# modular_expansion_system_esp32.net
KiCad netlist of a schematic drawn in EAGLE
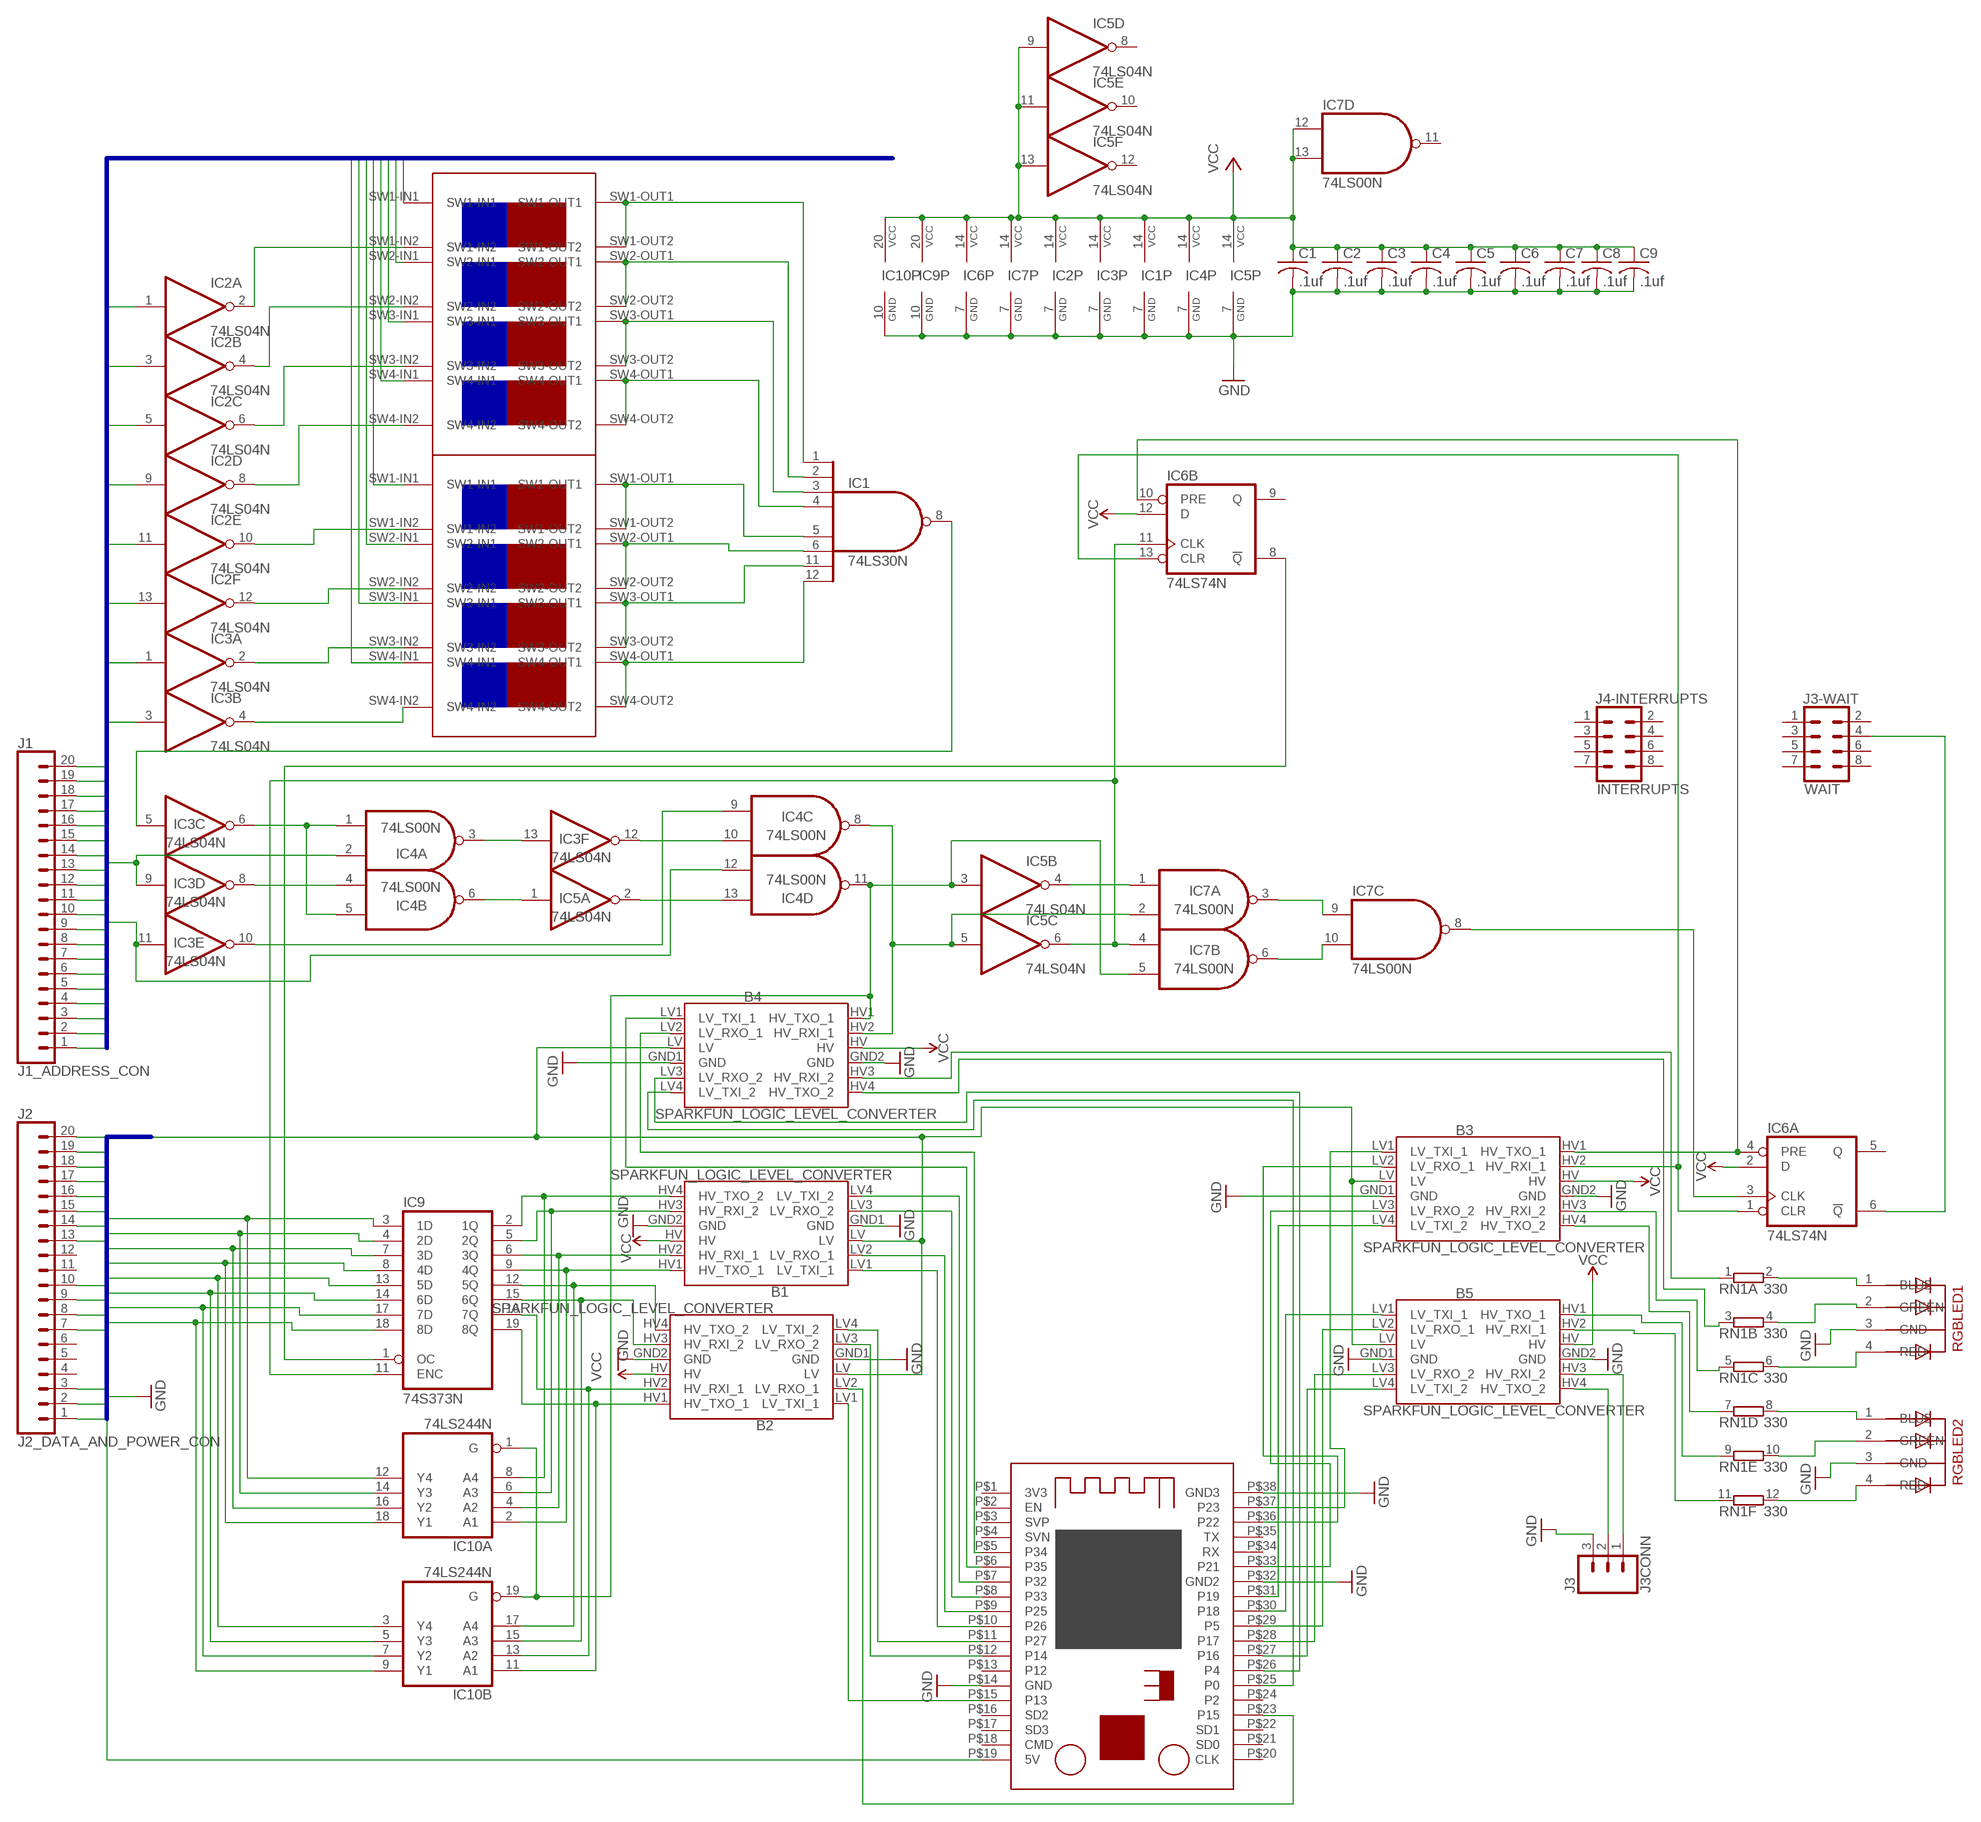
[diagram p0: schematic, sheet 1]

(export (version "E")
  (design (tool "Eeschema 10.0.6"))
  (components
    (comp (ref "B1")
      (value "SPARKFUN_LOGIC_LEVEL_CONVERTER")
      (footprint "eagle-import:SPARKFUN_LOGIC_LEVEL_CONVERTER")
      (libsource (lib "eagle-import") (part "SPARKFUN_LOGIC_LEVEL_CONVERTER"))
    )
    (comp (ref "B2")
      (value "SPARKFUN_LOGIC_LEVEL_CONVERTER")
      (footprint "eagle-import:SPARKFUN_LOGIC_LEVEL_CONVERTER")
      (libsource (lib "eagle-import") (part "SPARKFUN_LOGIC_LEVEL_CONVERTER"))
    )
    (comp (ref "B3")
      (value "SPARKFUN_LOGIC_LEVEL_CONVERTER")
      (footprint "eagle-import:SPARKFUN_LOGIC_LEVEL_CONVERTER")
      (libsource (lib "eagle-import") (part "SPARKFUN_LOGIC_LEVEL_CONVERTER"))
    )
    (comp (ref "B4")
      (value "SPARKFUN_LOGIC_LEVEL_CONVERTER")
      (footprint "eagle-import:SPARKFUN_LOGIC_LEVEL_CONVERTER")
      (libsource (lib "eagle-import") (part "SPARKFUN_LOGIC_LEVEL_CONVERTER"))
    )
    (comp (ref "B5")
      (value "SPARKFUN_LOGIC_LEVEL_CONVERTER")
      (footprint "eagle-import:SPARKFUN_LOGIC_LEVEL_CONVERTER")
      (libsource (lib "eagle-import") (part "SPARKFUN_LOGIC_LEVEL_CONVERTER"))
    )
    (comp (ref "C1")
      (value ".1uf")
      (footprint "eagle-import:C025-025X050")
      (libsource (lib "eagle-import") (part "C-US025-025X050"))
    )
    (comp (ref "C2")
      (value ".1uf")
      (footprint "eagle-import:C025-025X050")
      (libsource (lib "eagle-import") (part "C-US025-025X050"))
    )
    (comp (ref "C3")
      (value ".1uf")
      (footprint "eagle-import:C025-025X050")
      (libsource (lib "eagle-import") (part "C-US025-025X050"))
    )
    (comp (ref "C4")
      (value ".1uf")
      (footprint "eagle-import:C025-025X050")
      (libsource (lib "eagle-import") (part "C-US025-025X050"))
    )
    (comp (ref "C5")
      (value ".1uf")
      (footprint "eagle-import:C025-025X050")
      (libsource (lib "eagle-import") (part "C-US025-025X050"))
    )
    (comp (ref "C6")
      (value ".1uf")
      (footprint "eagle-import:C025-025X050")
      (libsource (lib "eagle-import") (part "C-US025-025X050"))
    )
    (comp (ref "C7")
      (value ".1uf")
      (footprint "eagle-import:C025-025X050")
      (libsource (lib "eagle-import") (part "C-US025-025X050"))
    )
    (comp (ref "C8")
      (value ".1uf")
      (footprint "eagle-import:C025-025X050")
      (libsource (lib "eagle-import") (part "C-US025-025X050"))
    )
    (comp (ref "C9")
      (value ".1uf")
      (footprint "eagle-import:C025-025X050")
      (libsource (lib "eagle-import") (part "C-US025-025X050"))
    )
    (comp (ref "IC1")
      (value "74LS30N")
      (footprint "eagle-import:DIL14")
      (libsource (lib "eagle-import") (part "7430NLS"))
    )
    (comp (ref "IC2")
      (value "74LS04N")
      (footprint "eagle-import:DIL14")
      (libsource (lib "eagle-import") (part "7404NLS"))
    )
    (comp (ref "IC3")
      (value "74LS04N")
      (footprint "eagle-import:DIL14")
      (libsource (lib "eagle-import") (part "7404NLS"))
    )
    (comp (ref "IC4")
      (value "74LS00N")
      (footprint "eagle-import:DIL14")
      (libsource (lib "eagle-import") (part "7400NLS"))
    )
    (comp (ref "IC5")
      (value "74LS04N")
      (footprint "eagle-import:DIL14")
      (libsource (lib "eagle-import") (part "7404NLS"))
    )
    (comp (ref "IC6")
      (value "74LS74N")
      (footprint "eagle-import:DIL14")
      (libsource (lib "eagle-import") (part "7474NLS"))
    )
    (comp (ref "IC7")
      (value "74LS00N")
      (footprint "eagle-import:DIL14")
      (libsource (lib "eagle-import") (part "7400NLS"))
    )
    (comp (ref "IC9")
      (value "74S373N")
      (footprint "eagle-import:DIL20")
      (libsource (lib "eagle-import") (part "74373NS"))
    )
    (comp (ref "IC10")
      (value "74LS244N")
      (footprint "eagle-import:DIL20")
      (libsource (lib "eagle-import") (part "74244NLS"))
    )
    (comp (ref "J1")
      (value "J1_ADDRESS_CON")
      (footprint "eagle-import:1X20")
      (libsource (lib "eagle-import") (part "CONN_20"))
    )
    (comp (ref "J2")
      (value "J2_DATA_AND_POWER_CON")
      (footprint "eagle-import:1X20")
      (libsource (lib "eagle-import") (part "CONN_20"))
    )
    (comp (ref "J3")
      (value "J3CONN")
      (footprint "eagle-import:1X03")
      (libsource (lib "eagle-import") (part "CONN_03"))
    )
    (comp (ref "J3-WAIT")
      (value "WAIT")
      (footprint "eagle-import:2X4")
      (libsource (lib "eagle-import") (part "CONN_04X2"))
    )
    (comp (ref "J4-INTERRUPTS")
      (value "INTERRUPTS")
      (footprint "eagle-import:2X4")
      (libsource (lib "eagle-import") (part "CONN_04X2"))
    )
    (comp (ref "RGBLED1")
      (value "5MMRGBLED")
      (footprint "eagle-import:LED5MMRGB")
      (libsource (lib "eagle-import") (part "5MMRGBLED"))
    )
    (comp (ref "RGBLED2")
      (value "5MMRGBLED")
      (footprint "eagle-import:LED5MMRGB")
      (libsource (lib "eagle-import") (part "5MMRGBLED"))
    )
    (comp (ref "RN1")
      (value "330")
      (footprint "eagle-import:SIL12")
      (libsource (lib "eagle-import") (part "E6R"))
    )
    (comp (ref "SW1")
      (value "CTS206-124")
      (footprint "eagle-import:CTS206-124")
      (libsource (lib "eagle-import") (part "CTS206-124"))
    )
    (comp (ref "SW2")
      (value "CTS206-124")
      (footprint "eagle-import:CTS206-124")
      (libsource (lib "eagle-import") (part "CTS206-124"))
    )
    (comp (ref "U$1")
      (value "ESP32S")
      (footprint "eagle-import:ESP32S")
      (libsource (lib "eagle-import") (part "ESP32S"))
    )
  )
  (nets
    (net (code "1") (name "/A0") (class "Default")
      (node (ref "IC3") (pin "3") (pinfunction "I_3") (pintype "input"))
      (node (ref "J1") (pin "1") (pinfunction "1_1") (pintype "passive"))
      (node (ref "SW1") (pin "SW4-IN1") (pinfunction "SW4-IN1_SW4-IN1") (pintype "bidirectional"))
    )
    (net (code "2") (name "/A1") (class "Default")
      (node (ref "IC3") (pin "1") (pinfunction "I_1") (pintype "input"))
      (node (ref "J1") (pin "2") (pinfunction "2_2") (pintype "passive"))
      (node (ref "SW1") (pin "SW3-IN1") (pinfunction "SW3-IN1_SW3-IN1") (pintype "bidirectional"))
    )
    (net (code "3") (name "/A2") (class "Default")
      (node (ref "IC2") (pin "13") (pinfunction "I_13") (pintype "input"))
      (node (ref "J1") (pin "3") (pinfunction "3_3") (pintype "passive"))
      (node (ref "SW1") (pin "SW2-IN1") (pinfunction "SW2-IN1_SW2-IN1") (pintype "bidirectional"))
    )
    (net (code "4") (name "/A3") (class "Default")
      (node (ref "IC2") (pin "11") (pinfunction "I_11") (pintype "input"))
      (node (ref "J1") (pin "4") (pinfunction "4_4") (pintype "passive"))
      (node (ref "SW1") (pin "SW1-IN1") (pinfunction "SW1-IN1_SW1-IN1") (pintype "bidirectional"))
    )
    (net (code "5") (name "/A4") (class "Default")
      (node (ref "IC2") (pin "9") (pinfunction "I_9") (pintype "input"))
      (node (ref "J1") (pin "5") (pinfunction "5_5") (pintype "passive"))
      (node (ref "SW2") (pin "SW4-IN1") (pinfunction "SW4-IN1_SW4-IN1") (pintype "bidirectional"))
    )
    (net (code "6") (name "/A5") (class "Default")
      (node (ref "IC2") (pin "5") (pinfunction "I_5") (pintype "input"))
      (node (ref "J1") (pin "6") (pinfunction "6_6") (pintype "passive"))
      (node (ref "SW2") (pin "SW3-IN1") (pinfunction "SW3-IN1_SW3-IN1") (pintype "bidirectional"))
    )
    (net (code "7") (name "/A6") (class "Default")
      (node (ref "IC2") (pin "3") (pinfunction "I_3") (pintype "input"))
      (node (ref "J1") (pin "7") (pinfunction "7_7") (pintype "passive"))
      (node (ref "SW2") (pin "SW2-IN1") (pinfunction "SW2-IN1_SW2-IN1") (pintype "bidirectional"))
    )
    (net (code "8") (name "/A7") (class "Default")
      (node (ref "IC2") (pin "1") (pinfunction "I_1") (pintype "input"))
      (node (ref "J1") (pin "8") (pinfunction "8_8") (pintype "passive"))
      (node (ref "SW2") (pin "SW1-IN1") (pinfunction "SW1-IN1_SW1-IN1") (pintype "bidirectional"))
    )
    (net (code "9") (name "/D0") (class "Default")
      (node (ref "IC10") (pin "9") (pinfunction "Y1_9") (pintype "tri_state"))
      (node (ref "IC9") (pin "18") (pinfunction "8D_18") (pintype "input"))
      (node (ref "J2") (pin "20") (pinfunction "20_20") (pintype "passive"))
    )
    (net (code "10") (name "/D1") (class "Default")
      (node (ref "IC10") (pin "7") (pinfunction "Y2_7") (pintype "tri_state"))
      (node (ref "IC9") (pin "17") (pinfunction "7D_17") (pintype "input"))
      (node (ref "J2") (pin "19") (pinfunction "19_19") (pintype "passive"))
    )
    (net (code "11") (name "/D2") (class "Default")
      (node (ref "IC10") (pin "5") (pinfunction "Y3_5") (pintype "tri_state"))
      (node (ref "IC9") (pin "14") (pinfunction "6D_14") (pintype "input"))
      (node (ref "J2") (pin "18") (pinfunction "18_18") (pintype "passive"))
    )
    (net (code "12") (name "/D3") (class "Default")
      (node (ref "IC10") (pin "3") (pinfunction "Y4_3") (pintype "tri_state"))
      (node (ref "IC9") (pin "13") (pinfunction "5D_13") (pintype "input"))
      (node (ref "J2") (pin "17") (pinfunction "17_17") (pintype "passive"))
    )
    (net (code "13") (name "/D4") (class "Default")
      (node (ref "IC10") (pin "18") (pinfunction "Y1_18") (pintype "tri_state"))
      (node (ref "IC9") (pin "8") (pinfunction "4D_8") (pintype "input"))
      (node (ref "J2") (pin "16") (pinfunction "16_16") (pintype "passive"))
    )
    (net (code "14") (name "/D5") (class "Default")
      (node (ref "IC10") (pin "16") (pinfunction "Y2_16") (pintype "tri_state"))
      (node (ref "IC9") (pin "7") (pinfunction "3D_7") (pintype "input"))
      (node (ref "J2") (pin "15") (pinfunction "15_15") (pintype "passive"))
    )
    (net (code "15") (name "/D6") (class "Default")
      (node (ref "IC10") (pin "14") (pinfunction "Y3_14") (pintype "tri_state"))
      (node (ref "IC9") (pin "4") (pinfunction "2D_4") (pintype "input"))
      (node (ref "J2") (pin "14") (pinfunction "14_14") (pintype "passive"))
    )
    (net (code "16") (name "/D7") (class "Default")
      (node (ref "IC10") (pin "12") (pinfunction "Y4_12") (pintype "tri_state"))
      (node (ref "IC9") (pin "3") (pinfunction "1D_3") (pintype "input"))
      (node (ref "J2") (pin "13") (pinfunction "13_13") (pintype "passive"))
    )
    (net (code "17") (name "/IN_") (class "Default")
      (node (ref "IC3") (pin "9") (pinfunction "I_9") (pintype "input"))
      (node (ref "IC4") (pin "2") (pinfunction "I1_2") (pintype "input"))
      (node (ref "J1") (pin "17") (pinfunction "17_17") (pintype "passive"))
    )
    (net (code "18") (name "/OUT_") (class "Default")
      (node (ref "IC3") (pin "11") (pinfunction "I_11") (pintype "input"))
      (node (ref "IC4") (pin "12") (pinfunction "I0_12") (pintype "input"))
      (node (ref "J1") (pin "18") (pinfunction "18_18") (pintype "passive"))
    )
    (net (code "19") (name "/VCC{slash}2") (class "Default")
      (node (ref "B1") (pin "LV") (pinfunction "LV_LV") (pintype "power_in"))
      (node (ref "B2") (pin "LV") (pinfunction "LV_LV") (pintype "power_in"))
      (node (ref "B3") (pin "LV") (pinfunction "LV_LV") (pintype "power_in"))
      (node (ref "B4") (pin "LV") (pinfunction "LV_LV") (pintype "power_in"))
      (node (ref "B5") (pin "LV") (pinfunction "LV_LV") (pintype "power_in"))
      (node (ref "J2") (pin "3") (pinfunction "3_3") (pintype "passive"))
    )
    (net (code "20") (name "GND") (class "Default")
      (node (ref "B1") (pin "GND1") (pinfunction "GND_GND1") (pintype "power_in"))
      (node (ref "B1") (pin "GND2") (pinfunction "GND_GND2") (pintype "power_in"))
      (node (ref "B2") (pin "GND1") (pinfunction "GND_GND1") (pintype "power_in"))
      (node (ref "B2") (pin "GND2") (pinfunction "GND_GND2") (pintype "power_in"))
      (node (ref "B3") (pin "GND1") (pinfunction "GND_GND1") (pintype "power_in"))
      (node (ref "B3") (pin "GND2") (pinfunction "GND_GND2") (pintype "power_in"))
      (node (ref "B4") (pin "GND1") (pinfunction "GND_GND1") (pintype "power_in"))
      (node (ref "B4") (pin "GND2") (pinfunction "GND_GND2") (pintype "power_in"))
      (node (ref "B5") (pin "GND1") (pinfunction "GND_GND1") (pintype "power_in"))
      (node (ref "B5") (pin "GND2") (pinfunction "GND_GND2") (pintype "power_in"))
      (node (ref "C1") (pin "2") (pinfunction "2_2") (pintype "passive"))
      (node (ref "C2") (pin "2") (pinfunction "2_2") (pintype "passive"))
      (node (ref "C3") (pin "2") (pinfunction "2_2") (pintype "passive"))
      (node (ref "C4") (pin "2") (pinfunction "2_2") (pintype "passive"))
      (node (ref "C5") (pin "2") (pinfunction "2_2") (pintype "passive"))
      (node (ref "C6") (pin "2") (pinfunction "2_2") (pintype "passive"))
      (node (ref "C7") (pin "2") (pinfunction "2_2") (pintype "passive"))
      (node (ref "C8") (pin "2") (pinfunction "2_2") (pintype "passive"))
      (node (ref "C9") (pin "2") (pinfunction "2_2") (pintype "passive"))
      (node (ref "IC1") (pin "7") (pinfunction "GND_7") (pintype "power_in"))
      (node (ref "IC10") (pin "10") (pinfunction "GND_10") (pintype "power_in"))
      (node (ref "IC2") (pin "7") (pinfunction "GND_7") (pintype "power_in"))
      (node (ref "IC3") (pin "7") (pinfunction "GND_7") (pintype "power_in"))
      (node (ref "IC4") (pin "7") (pinfunction "GND_7") (pintype "power_in"))
      (node (ref "IC5") (pin "7") (pinfunction "GND_7") (pintype "power_in"))
      (node (ref "IC6") (pin "7") (pinfunction "GND_7") (pintype "power_in"))
      (node (ref "IC7") (pin "7") (pinfunction "GND_7") (pintype "power_in"))
      (node (ref "IC9") (pin "10") (pinfunction "GND_10") (pintype "power_in"))
      (node (ref "J2") (pin "2") (pinfunction "2_2") (pintype "passive"))
      (node (ref "J3") (pin "3") (pinfunction "3_3") (pintype "passive"))
      (node (ref "RGBLED1") (pin "3") (pinfunction "GND_3") (pintype "bidirectional"))
      (node (ref "RGBLED2") (pin "3") (pinfunction "GND_3") (pintype "bidirectional"))
      (node (ref "U$1") (pin "P$14") (pinfunction "GND_P$14") (pintype "bidirectional"))
      (node (ref "U$1") (pin "P$32") (pinfunction "GND2_P$32") (pintype "bidirectional"))
      (node (ref "U$1") (pin "P$38") (pinfunction "GND3_P$38") (pintype "bidirectional"))
    )
    (net (code "21") (name "Net-(B1-HV_RXI_1)") (class "Default")
      (node (ref "B1") (pin "HV2") (pinfunction "HV_RXI_1_HV2") (pintype "bidirectional"))
      (node (ref "IC10") (pin "4") (pinfunction "A2_4") (pintype "input"))
      (node (ref "IC9") (pin "6") (pinfunction "3Q_6") (pintype "tri_state"))
    )
    (net (code "22") (name "Net-(B1-HV_RXI_2)") (class "Default")
      (node (ref "B1") (pin "HV3") (pinfunction "HV_RXI_2_HV3") (pintype "bidirectional"))
      (node (ref "IC10") (pin "6") (pinfunction "A3_6") (pintype "input"))
      (node (ref "IC9") (pin "5") (pinfunction "2Q_5") (pintype "tri_state"))
    )
    (net (code "23") (name "Net-(B1-HV_TXO_1)") (class "Default")
      (node (ref "B1") (pin "HV1") (pinfunction "HV_TXO_1_HV1") (pintype "bidirectional"))
      (node (ref "IC10") (pin "2") (pinfunction "A1_2") (pintype "input"))
      (node (ref "IC9") (pin "9") (pinfunction "4Q_9") (pintype "tri_state"))
    )
    (net (code "24") (name "Net-(B1-HV_TXO_2)") (class "Default")
      (node (ref "B1") (pin "HV4") (pinfunction "HV_TXO_2_HV4") (pintype "bidirectional"))
      (node (ref "IC10") (pin "8") (pinfunction "A4_8") (pintype "input"))
      (node (ref "IC9") (pin "2") (pinfunction "1Q_2") (pintype "tri_state"))
    )
    (net (code "25") (name "Net-(B1-LV_RXO_1)") (class "Default")
      (node (ref "B1") (pin "LV2") (pinfunction "LV_RXO_1_LV2") (pintype "bidirectional"))
      (node (ref "U$1") (pin "P$9") (pinfunction "P25_P$9") (pintype "bidirectional"))
    )
    (net (code "26") (name "Net-(B1-LV_RXO_2)") (class "Default")
      (node (ref "B1") (pin "LV3") (pinfunction "LV_RXO_2_LV3") (pintype "bidirectional"))
      (node (ref "U$1") (pin "P$8") (pinfunction "P33_P$8") (pintype "bidirectional"))
    )
    (net (code "27") (name "Net-(B1-LV_TXI_1)") (class "Default")
      (node (ref "B1") (pin "LV1") (pinfunction "LV_TXI_1_LV1") (pintype "bidirectional"))
      (node (ref "U$1") (pin "P$10") (pinfunction "P26_P$10") (pintype "bidirectional"))
    )
    (net (code "28") (name "Net-(B1-LV_TXI_2)") (class "Default")
      (node (ref "B1") (pin "LV4") (pinfunction "LV_TXI_2_LV4") (pintype "bidirectional"))
      (node (ref "U$1") (pin "P$7") (pinfunction "P32_P$7") (pintype "bidirectional"))
    )
    (net (code "29") (name "Net-(B2-HV_RXI_1)") (class "Default")
      (node (ref "B2") (pin "HV2") (pinfunction "HV_RXI_1_HV2") (pintype "bidirectional"))
      (node (ref "IC10") (pin "13") (pinfunction "A2_13") (pintype "input"))
      (node (ref "IC9") (pin "16") (pinfunction "7Q_16") (pintype "tri_state"))
    )
    (net (code "30") (name "Net-(B2-HV_RXI_2)") (class "Default")
      (node (ref "B2") (pin "HV3") (pinfunction "HV_RXI_2_HV3") (pintype "bidirectional"))
      (node (ref "IC10") (pin "15") (pinfunction "A3_15") (pintype "input"))
      (node (ref "IC9") (pin "15") (pinfunction "6Q_15") (pintype "tri_state"))
    )
    (net (code "31") (name "Net-(B2-HV_TXO_1)") (class "Default")
      (node (ref "B2") (pin "HV1") (pinfunction "HV_TXO_1_HV1") (pintype "bidirectional"))
      (node (ref "IC10") (pin "11") (pinfunction "A1_11") (pintype "input"))
      (node (ref "IC9") (pin "19") (pinfunction "8Q_19") (pintype "tri_state"))
    )
    (net (code "32") (name "Net-(B2-HV_TXO_2)") (class "Default")
      (node (ref "B2") (pin "HV4") (pinfunction "HV_TXO_2_HV4") (pintype "bidirectional"))
      (node (ref "IC10") (pin "17") (pinfunction "A4_17") (pintype "input"))
      (node (ref "IC9") (pin "12") (pinfunction "5Q_12") (pintype "tri_state"))
    )
    (net (code "33") (name "Net-(B2-LV_RXO_1)") (class "Default")
      (node (ref "B2") (pin "LV2") (pinfunction "LV_RXO_1_LV2") (pintype "bidirectional"))
      (node (ref "U$1") (pin "P$23") (pinfunction "P15_P$23") (pintype "bidirectional"))
    )
    (net (code "34") (name "Net-(B2-LV_RXO_2)") (class "Default")
      (node (ref "B2") (pin "LV3") (pinfunction "LV_RXO_2_LV3") (pintype "bidirectional"))
      (node (ref "U$1") (pin "P$12") (pinfunction "P14_P$12") (pintype "bidirectional"))
    )
    (net (code "35") (name "Net-(B2-LV_TXI_1)") (class "Default")
      (node (ref "B2") (pin "LV1") (pinfunction "LV_TXI_1_LV1") (pintype "bidirectional"))
      (node (ref "U$1") (pin "P$15") (pinfunction "P13_P$15") (pintype "bidirectional"))
    )
    (net (code "36") (name "Net-(B2-LV_TXI_2)") (class "Default")
      (node (ref "B2") (pin "LV4") (pinfunction "LV_TXI_2_LV4") (pintype "bidirectional"))
      (node (ref "U$1") (pin "P$11") (pinfunction "P27_P$11") (pintype "bidirectional"))
    )
    (net (code "37") (name "Net-(B3-HV_RXI_1)") (class "Default")
      (node (ref "B3") (pin "HV2") (pinfunction "HV_RXI_1_HV2") (pintype "bidirectional"))
      (node (ref "IC6") (pin "1") (pinfunction "CLR_1") (pintype "input"))
      (node (ref "IC6") (pin "13") (pinfunction "CLR_13") (pintype "input"))
    )
    (net (code "38") (name "Net-(B3-HV_RXI_2)") (class "Default")
      (node (ref "B3") (pin "HV3") (pinfunction "HV_RXI_2_HV3") (pintype "bidirectional"))
      (node (ref "RN1") (pin "5") (pinfunction "1_5") (pintype "passive"))
    )
    (net (code "39") (name "Net-(B3-HV_TXO_1)") (class "Default")
      (node (ref "B3") (pin "HV1") (pinfunction "HV_TXO_1_HV1") (pintype "bidirectional"))
      (node (ref "IC6") (pin "10") (pinfunction "PRE_10") (pintype "input"))
      (node (ref "IC6") (pin "4") (pinfunction "PRE_4") (pintype "input"))
    )
    (net (code "40") (name "Net-(B3-HV_TXO_2)") (class "Default")
      (node (ref "B3") (pin "HV4") (pinfunction "HV_TXO_2_HV4") (pintype "bidirectional"))
      (node (ref "RN1") (pin "7") (pinfunction "1_7") (pintype "passive"))
    )
    (net (code "41") (name "Net-(B3-LV_RXO_1)") (class "Default")
      (node (ref "B3") (pin "LV2") (pinfunction "LV_RXO_1_LV2") (pintype "bidirectional"))
      (node (ref "U$1") (pin "P$36") (pinfunction "P22_P$36") (pintype "bidirectional"))
    )
    (net (code "42") (name "Net-(B3-LV_RXO_2)") (class "Default")
      (node (ref "B3") (pin "LV3") (pinfunction "LV_RXO_2_LV3") (pintype "bidirectional"))
      (node (ref "U$1") (pin "P$33") (pinfunction "P21_P$33") (pintype "bidirectional"))
    )
    (net (code "43") (name "Net-(B3-LV_TXI_1)") (class "Default")
      (node (ref "B3") (pin "LV1") (pinfunction "LV_TXI_1_LV1") (pintype "bidirectional"))
      (node (ref "U$1") (pin "P$37") (pinfunction "P23_P$37") (pintype "bidirectional"))
    )
    (net (code "44") (name "Net-(B3-LV_TXI_2)") (class "Default")
      (node (ref "B3") (pin "LV4") (pinfunction "LV_TXI_2_LV4") (pintype "bidirectional"))
      (node (ref "U$1") (pin "P$31") (pinfunction "P19_P$31") (pintype "bidirectional"))
    )
    (net (code "45") (name "Net-(B4-HV_RXI_1)") (class "Default")
      (node (ref "B4") (pin "HV2") (pinfunction "HV_RXI_1_HV2") (pintype "bidirectional"))
      (node (ref "IC4") (pin "8") (pinfunction "O_8") (pintype "output"))
      (node (ref "IC5") (pin "5") (pinfunction "I_5") (pintype "input"))
      (node (ref "IC7") (pin "2") (pinfunction "I1_2") (pintype "input"))
    )
    (net (code "46") (name "Net-(B4-HV_RXI_2)") (class "Default")
      (node (ref "B4") (pin "HV3") (pinfunction "HV_RXI_2_HV3") (pintype "bidirectional"))
      (node (ref "RN1") (pin "1") (pinfunction "1_1") (pintype "passive"))
    )
    (net (code "47") (name "Net-(B4-HV_TXO_1)") (class "Default")
      (node (ref "B4") (pin "HV1") (pinfunction "HV_TXO_1_HV1") (pintype "bidirectional"))
      (node (ref "IC10") (pin "1") (pinfunction "G_1") (pintype "input"))
      (node (ref "IC10") (pin "19") (pinfunction "G_19") (pintype "input"))
      (node (ref "IC4") (pin "11") (pinfunction "O_11") (pintype "output"))
      (node (ref "IC5") (pin "3") (pinfunction "I_3") (pintype "input"))
      (node (ref "IC7") (pin "5") (pinfunction "I1_5") (pintype "input"))
    )
    (net (code "48") (name "Net-(B4-HV_TXO_2)") (class "Default")
      (node (ref "B4") (pin "HV4") (pinfunction "HV_TXO_2_HV4") (pintype "bidirectional"))
      (node (ref "RN1") (pin "3") (pinfunction "1_3") (pintype "passive"))
    )
    (net (code "49") (name "Net-(B4-LV_RXO_1)") (class "Default")
      (node (ref "B4") (pin "LV2") (pinfunction "LV_RXO_1_LV2") (pintype "bidirectional"))
      (node (ref "U$1") (pin "P$5") (pinfunction "P34_P$5") (pintype "bidirectional"))
    )
    (net (code "50") (name "Net-(B4-LV_RXO_2)") (class "Default")
      (node (ref "B4") (pin "LV3") (pinfunction "LV_RXO_2_LV3") (pintype "bidirectional"))
      (node (ref "U$1") (pin "P$26") (pinfunction "P4_P$26") (pintype "bidirectional"))
    )
    (net (code "51") (name "Net-(B4-LV_TXI_1)") (class "Default")
      (node (ref "B4") (pin "LV1") (pinfunction "LV_TXI_1_LV1") (pintype "bidirectional"))
      (node (ref "U$1") (pin "P$6") (pinfunction "P35_P$6") (pintype "bidirectional"))
    )
    (net (code "52") (name "Net-(B4-LV_TXI_2)") (class "Default")
      (node (ref "B4") (pin "LV4") (pinfunction "LV_TXI_2_LV4") (pintype "bidirectional"))
      (node (ref "U$1") (pin "P$25") (pinfunction "P0_P$25") (pintype "bidirectional"))
    )
    (net (code "53") (name "Net-(B5-HV_RXI_1)") (class "Default")
      (node (ref "B5") (pin "HV2") (pinfunction "HV_RXI_1_HV2") (pintype "bidirectional"))
      (node (ref "RN1") (pin "11") (pinfunction "1_11") (pintype "passive"))
    )
    (net (code "54") (name "Net-(B5-HV_RXI_2)") (class "Default")
      (node (ref "B5") (pin "HV3") (pinfunction "HV_RXI_2_HV3") (pintype "bidirectional"))
      (node (ref "J3") (pin "1") (pinfunction "1_1") (pintype "passive"))
    )
    (net (code "55") (name "Net-(B5-HV_TXO_1)") (class "Default")
      (node (ref "B5") (pin "HV1") (pinfunction "HV_TXO_1_HV1") (pintype "bidirectional"))
      (node (ref "RN1") (pin "9") (pinfunction "1_9") (pintype "passive"))
    )
    (net (code "56") (name "Net-(B5-HV_TXO_2)") (class "Default")
      (node (ref "B5") (pin "HV4") (pinfunction "HV_TXO_2_HV4") (pintype "bidirectional"))
      (node (ref "J3") (pin "2") (pinfunction "2_2") (pintype "passive"))
    )
    (net (code "57") (name "Net-(B5-LV_RXO_1)") (class "Default")
      (node (ref "B5") (pin "LV2") (pinfunction "LV_RXO_1_LV2") (pintype "bidirectional"))
      (node (ref "U$1") (pin "P$29") (pinfunction "P5_P$29") (pintype "bidirectional"))
    )
    (net (code "58") (name "Net-(B5-LV_RXO_2)") (class "Default")
      (node (ref "B5") (pin "LV3") (pinfunction "LV_RXO_2_LV3") (pintype "bidirectional"))
      (node (ref "U$1") (pin "P$28") (pinfunction "P17_P$28") (pintype "bidirectional"))
    )
    (net (code "59") (name "Net-(B5-LV_TXI_1)") (class "Default")
      (node (ref "B5") (pin "LV1") (pinfunction "LV_TXI_1_LV1") (pintype "bidirectional"))
      (node (ref "U$1") (pin "P$30") (pinfunction "P18_P$30") (pintype "bidirectional"))
    )
    (net (code "60") (name "Net-(B5-LV_TXI_2)") (class "Default")
      (node (ref "B5") (pin "LV4") (pinfunction "LV_TXI_2_LV4") (pintype "bidirectional"))
      (node (ref "U$1") (pin "P$27") (pinfunction "P16_P$27") (pintype "bidirectional"))
    )
    (net (code "61") (name "Net-(IC1A-I0)") (class "Default")
      (node (ref "IC1") (pin "1") (pinfunction "I0_1") (pintype "input"))
      (node (ref "SW2") (pin "SW1-OUT1") (pinfunction "SW1-OUT1_SW1-OUT1") (pintype "bidirectional"))
      (node (ref "SW2") (pin "SW1-OUT2") (pinfunction "SW1-OUT2_SW1-OUT2") (pintype "bidirectional"))
    )
    (net (code "62") (name "Net-(IC1A-I1)") (class "Default")
      (node (ref "IC1") (pin "2") (pinfunction "I1_2") (pintype "input"))
      (node (ref "SW2") (pin "SW2-OUT1") (pinfunction "SW2-OUT1_SW2-OUT1") (pintype "bidirectional"))
      (node (ref "SW2") (pin "SW2-OUT2") (pinfunction "SW2-OUT2_SW2-OUT2") (pintype "bidirectional"))
    )
    (net (code "63") (name "Net-(IC1A-I2)") (class "Default")
      (node (ref "IC1") (pin "3") (pinfunction "I2_3") (pintype "input"))
      (node (ref "SW2") (pin "SW3-OUT1") (pinfunction "SW3-OUT1_SW3-OUT1") (pintype "bidirectional"))
      (node (ref "SW2") (pin "SW3-OUT2") (pinfunction "SW3-OUT2_SW3-OUT2") (pintype "bidirectional"))
    )
    (net (code "64") (name "Net-(IC1A-I3)") (class "Default")
      (node (ref "IC1") (pin "4") (pinfunction "I3_4") (pintype "input"))
      (node (ref "SW2") (pin "SW4-OUT1") (pinfunction "SW4-OUT1_SW4-OUT1") (pintype "bidirectional"))
      (node (ref "SW2") (pin "SW4-OUT2") (pinfunction "SW4-OUT2_SW4-OUT2") (pintype "bidirectional"))
    )
    (net (code "65") (name "Net-(IC1A-I4)") (class "Default")
      (node (ref "IC1") (pin "5") (pinfunction "I4_5") (pintype "input"))
      (node (ref "SW1") (pin "SW1-OUT1") (pinfunction "SW1-OUT1_SW1-OUT1") (pintype "bidirectional"))
      (node (ref "SW1") (pin "SW1-OUT2") (pinfunction "SW1-OUT2_SW1-OUT2") (pintype "bidirectional"))
    )
    (net (code "66") (name "Net-(IC1A-I5)") (class "Default")
      (node (ref "IC1") (pin "6") (pinfunction "I5_6") (pintype "input"))
      (node (ref "SW1") (pin "SW2-OUT1") (pinfunction "SW2-OUT1_SW2-OUT1") (pintype "bidirectional"))
      (node (ref "SW1") (pin "SW2-OUT2") (pinfunction "SW2-OUT2_SW2-OUT2") (pintype "bidirectional"))
    )
    (net (code "67") (name "Net-(IC1A-I6)") (class "Default")
      (node (ref "IC1") (pin "11") (pinfunction "I6_11") (pintype "input"))
      (node (ref "SW1") (pin "SW3-OUT1") (pinfunction "SW3-OUT1_SW3-OUT1") (pintype "bidirectional"))
      (node (ref "SW1") (pin "SW3-OUT2") (pinfunction "SW3-OUT2_SW3-OUT2") (pintype "bidirectional"))
    )
    (net (code "68") (name "Net-(IC1A-I7)") (class "Default")
      (node (ref "IC1") (pin "12") (pinfunction "I7_12") (pintype "input"))
      (node (ref "SW1") (pin "SW4-OUT1") (pinfunction "SW4-OUT1_SW4-OUT1") (pintype "bidirectional"))
      (node (ref "SW1") (pin "SW4-OUT2") (pinfunction "SW4-OUT2_SW4-OUT2") (pintype "bidirectional"))
    )
    (net (code "69") (name "Net-(IC1A-O)") (class "Default")
      (node (ref "IC1") (pin "8") (pinfunction "O_8") (pintype "output"))
      (node (ref "IC3") (pin "5") (pinfunction "I_5") (pintype "input"))
    )
    (net (code "70") (name "Net-(IC2A-O)") (class "Default")
      (node (ref "IC2") (pin "2") (pinfunction "O_2") (pintype "output"))
      (node (ref "SW2") (pin "SW1-IN2") (pinfunction "SW1-IN2_SW1-IN2") (pintype "bidirectional"))
    )
    (net (code "71") (name "Net-(IC2B-O)") (class "Default")
      (node (ref "IC2") (pin "4") (pinfunction "O_4") (pintype "output"))
      (node (ref "SW2") (pin "SW2-IN2") (pinfunction "SW2-IN2_SW2-IN2") (pintype "bidirectional"))
    )
    (net (code "72") (name "Net-(IC2C-O)") (class "Default")
      (node (ref "IC2") (pin "6") (pinfunction "O_6") (pintype "output"))
      (node (ref "SW2") (pin "SW3-IN2") (pinfunction "SW3-IN2_SW3-IN2") (pintype "bidirectional"))
    )
    (net (code "73") (name "Net-(IC2D-O)") (class "Default")
      (node (ref "IC2") (pin "8") (pinfunction "O_8") (pintype "output"))
      (node (ref "SW2") (pin "SW4-IN2") (pinfunction "SW4-IN2_SW4-IN2") (pintype "bidirectional"))
    )
    (net (code "74") (name "Net-(IC2E-O)") (class "Default")
      (node (ref "IC2") (pin "10") (pinfunction "O_10") (pintype "output"))
      (node (ref "SW1") (pin "SW1-IN2") (pinfunction "SW1-IN2_SW1-IN2") (pintype "bidirectional"))
    )
    (net (code "75") (name "Net-(IC2F-O)") (class "Default")
      (node (ref "IC2") (pin "12") (pinfunction "O_12") (pintype "output"))
      (node (ref "SW1") (pin "SW2-IN2") (pinfunction "SW2-IN2_SW2-IN2") (pintype "bidirectional"))
    )
    (net (code "76") (name "Net-(IC3A-O)") (class "Default")
      (node (ref "IC3") (pin "2") (pinfunction "O_2") (pintype "output"))
      (node (ref "SW1") (pin "SW3-IN2") (pinfunction "SW3-IN2_SW3-IN2") (pintype "bidirectional"))
    )
    (net (code "77") (name "Net-(IC3B-O)") (class "Default")
      (node (ref "IC3") (pin "4") (pinfunction "O_4") (pintype "output"))
      (node (ref "SW1") (pin "SW4-IN2") (pinfunction "SW4-IN2_SW4-IN2") (pintype "bidirectional"))
    )
    (net (code "78") (name "Net-(IC3C-O)") (class "Default")
      (node (ref "IC3") (pin "6") (pinfunction "O_6") (pintype "output"))
      (node (ref "IC4") (pin "1") (pinfunction "I0_1") (pintype "input"))
      (node (ref "IC4") (pin "5") (pinfunction "I1_5") (pintype "input"))
    )
    (net (code "79") (name "Net-(IC3D-O)") (class "Default")
      (node (ref "IC3") (pin "8") (pinfunction "O_8") (pintype "output"))
      (node (ref "IC4") (pin "4") (pinfunction "I0_4") (pintype "input"))
    )
    (net (code "80") (name "Net-(IC3E-O)") (class "Default")
      (node (ref "IC3") (pin "10") (pinfunction "O_10") (pintype "output"))
      (node (ref "IC4") (pin "9") (pinfunction "I0_9") (pintype "input"))
    )
    (net (code "81") (name "Net-(IC3F-I)") (class "Default")
      (node (ref "IC3") (pin "13") (pinfunction "I_13") (pintype "input"))
      (node (ref "IC4") (pin "3") (pinfunction "O_3") (pintype "output"))
    )
    (net (code "82") (name "Net-(IC3F-O)") (class "Default")
      (node (ref "IC3") (pin "12") (pinfunction "O_12") (pintype "output"))
      (node (ref "IC4") (pin "10") (pinfunction "I1_10") (pintype "input"))
    )
    (net (code "83") (name "Net-(IC4B-O)") (class "Default")
      (node (ref "IC4") (pin "6") (pinfunction "O_6") (pintype "output"))
      (node (ref "IC5") (pin "1") (pinfunction "I_1") (pintype "input"))
    )
    (net (code "84") (name "Net-(IC4D-I1)") (class "Default")
      (node (ref "IC4") (pin "13") (pinfunction "I1_13") (pintype "input"))
      (node (ref "IC5") (pin "2") (pinfunction "O_2") (pintype "output"))
    )
    (net (code "85") (name "Net-(IC5B-O)") (class "Default")
      (node (ref "IC5") (pin "4") (pinfunction "O_4") (pintype "output"))
      (node (ref "IC7") (pin "1") (pinfunction "I0_1") (pintype "input"))
    )
    (net (code "86") (name "Net-(IC5C-O)") (class "Default")
      (node (ref "IC5") (pin "6") (pinfunction "O_6") (pintype "output"))
      (node (ref "IC6") (pin "11") (pinfunction "CLK_11") (pintype "input"))
      (node (ref "IC7") (pin "4") (pinfunction "I0_4") (pintype "input"))
      (node (ref "IC9") (pin "11") (pinfunction "ENC_11") (pintype "input"))
    )
    (net (code "87") (name "Net-(IC6A-CLK)") (class "Default")
      (node (ref "IC6") (pin "3") (pinfunction "CLK_3") (pintype "input"))
      (node (ref "IC7") (pin "8") (pinfunction "O_8") (pintype "output"))
    )
    (net (code "88") (name "Net-(IC6A-~{Q})") (class "Default")
      (node (ref "IC6") (pin "6") (pinfunction "~{Q}_6") (pintype "output"))
      (node (ref "J3-WAIT") (pin "4") (pinfunction "4_4") (pintype "passive"))
    )
    (net (code "89") (name "Net-(IC6B-~{Q})") (class "Default")
      (node (ref "IC6") (pin "8") (pinfunction "~{Q}_8") (pintype "output"))
      (node (ref "IC9") (pin "1") (pinfunction "OC_1") (pintype "input"))
    )
    (net (code "90") (name "Net-(IC7A-O)") (class "Default")
      (node (ref "IC7") (pin "3") (pinfunction "O_3") (pintype "output"))
      (node (ref "IC7") (pin "9") (pinfunction "I0_9") (pintype "input"))
    )
    (net (code "91") (name "Net-(IC7B-O)") (class "Default")
      (node (ref "IC7") (pin "10") (pinfunction "I1_10") (pintype "input"))
      (node (ref "IC7") (pin "6") (pinfunction "O_6") (pintype "output"))
    )
    (net (code "92") (name "Net-(RGBLED1-BLUE)") (class "Default")
      (node (ref "RGBLED1") (pin "1") (pinfunction "BLUE_1") (pintype "bidirectional"))
      (node (ref "RN1") (pin "2") (pinfunction "2_2") (pintype "passive"))
    )
    (net (code "93") (name "Net-(RGBLED1-GREEN)") (class "Default")
      (node (ref "RGBLED1") (pin "2") (pinfunction "GREEN_2") (pintype "bidirectional"))
      (node (ref "RN1") (pin "4") (pinfunction "2_4") (pintype "passive"))
    )
    (net (code "94") (name "Net-(RGBLED1-RED)") (class "Default")
      (node (ref "RGBLED1") (pin "4") (pinfunction "RED_4") (pintype "bidirectional"))
      (node (ref "RN1") (pin "6") (pinfunction "2_6") (pintype "passive"))
    )
    (net (code "95") (name "Net-(RGBLED2-BLUE)") (class "Default")
      (node (ref "RGBLED2") (pin "1") (pinfunction "BLUE_1") (pintype "bidirectional"))
      (node (ref "RN1") (pin "8") (pinfunction "2_8") (pintype "passive"))
    )
    (net (code "96") (name "Net-(RGBLED2-GREEN)") (class "Default")
      (node (ref "RGBLED2") (pin "2") (pinfunction "GREEN_2") (pintype "bidirectional"))
      (node (ref "RN1") (pin "10") (pinfunction "2_10") (pintype "passive"))
    )
    (net (code "97") (name "Net-(RGBLED2-RED)") (class "Default")
      (node (ref "RGBLED2") (pin "4") (pinfunction "RED_4") (pintype "bidirectional"))
      (node (ref "RN1") (pin "12") (pinfunction "2_12") (pintype "passive"))
    )
    (net (code "98") (name "VCC") (class "Default")
      (node (ref "B1") (pin "HV") (pinfunction "HV_HV") (pintype "power_in"))
      (node (ref "B2") (pin "HV") (pinfunction "HV_HV") (pintype "power_in"))
      (node (ref "B3") (pin "HV") (pinfunction "HV_HV") (pintype "power_in"))
      (node (ref "B4") (pin "HV") (pinfunction "HV_HV") (pintype "power_in"))
      (node (ref "B5") (pin "HV") (pinfunction "HV_HV") (pintype "power_in"))
      (node (ref "C1") (pin "1") (pinfunction "1_1") (pintype "passive"))
      (node (ref "C2") (pin "1") (pinfunction "1_1") (pintype "passive"))
      (node (ref "C3") (pin "1") (pinfunction "1_1") (pintype "passive"))
      (node (ref "C4") (pin "1") (pinfunction "1_1") (pintype "passive"))
      (node (ref "C5") (pin "1") (pinfunction "1_1") (pintype "passive"))
      (node (ref "C6") (pin "1") (pinfunction "1_1") (pintype "passive"))
      (node (ref "C7") (pin "1") (pinfunction "1_1") (pintype "passive"))
      (node (ref "C8") (pin "1") (pinfunction "1_1") (pintype "passive"))
      (node (ref "C9") (pin "1") (pinfunction "1_1") (pintype "passive"))
      (node (ref "IC1") (pin "14") (pinfunction "VCC_14") (pintype "power_in"))
      (node (ref "IC10") (pin "20") (pinfunction "VCC_20") (pintype "power_in"))
      (node (ref "IC2") (pin "14") (pinfunction "VCC_14") (pintype "power_in"))
      (node (ref "IC3") (pin "14") (pinfunction "VCC_14") (pintype "power_in"))
      (node (ref "IC4") (pin "14") (pinfunction "VCC_14") (pintype "power_in"))
      (node (ref "IC5") (pin "11") (pinfunction "I_11") (pintype "input"))
      (node (ref "IC5") (pin "13") (pinfunction "I_13") (pintype "input"))
      (node (ref "IC5") (pin "14") (pinfunction "VCC_14") (pintype "power_in"))
      (node (ref "IC5") (pin "9") (pinfunction "I_9") (pintype "input"))
      (node (ref "IC6") (pin "12") (pinfunction "D_12") (pintype "input"))
      (node (ref "IC6") (pin "14") (pinfunction "VCC_14") (pintype "power_in"))
      (node (ref "IC6") (pin "2") (pinfunction "D_2") (pintype "input"))
      (node (ref "IC7") (pin "12") (pinfunction "I0_12") (pintype "input"))
      (node (ref "IC7") (pin "13") (pinfunction "I1_13") (pintype "input"))
      (node (ref "IC7") (pin "14") (pinfunction "VCC_14") (pintype "power_in"))
      (node (ref "IC9") (pin "20") (pinfunction "VCC_20") (pintype "power_in"))
      (node (ref "J2") (pin "1") (pinfunction "1_1") (pintype "passive"))
      (node (ref "U$1") (pin "P$19") (pinfunction "5V_P$19") (pintype "bidirectional"))
    )
    (net (code "99") (name "unconnected-(IC5D-O-Pad8)") (class "Default")
      (node (ref "IC5") (pin "8") (pinfunction "O_8") (pintype "output"))
    )
    (net (code "100") (name "unconnected-(IC5E-O-Pad10)") (class "Default")
      (node (ref "IC5") (pin "10") (pinfunction "O_10") (pintype "output"))
    )
    (net (code "101") (name "unconnected-(IC5F-O-Pad12)") (class "Default")
      (node (ref "IC5") (pin "12") (pinfunction "O_12") (pintype "output"))
    )
    (net (code "102") (name "unconnected-(IC6A-Q-Pad5)") (class "Default")
      (node (ref "IC6") (pin "5") (pinfunction "Q_5") (pintype "output"))
    )
    (net (code "103") (name "unconnected-(IC6B-Q-Pad9)") (class "Default")
      (node (ref "IC6") (pin "9") (pinfunction "Q_9") (pintype "output"))
    )
    (net (code "104") (name "unconnected-(IC7D-O-Pad11)") (class "Default")
      (node (ref "IC7") (pin "11") (pinfunction "O_11") (pintype "output"))
    )
    (net (code "105") (name "unconnected-(J1-Pad9)") (class "Default")
      (node (ref "J1") (pin "9") (pinfunction "9_9") (pintype "passive"))
    )
    (net (code "106") (name "unconnected-(J1-Pad10)") (class "Default")
      (node (ref "J1") (pin "10") (pinfunction "10_10") (pintype "passive"))
    )
    (net (code "107") (name "unconnected-(J1-Pad11)") (class "Default")
      (node (ref "J1") (pin "11") (pinfunction "11_11") (pintype "passive"))
    )
    (net (code "108") (name "unconnected-(J1-Pad12)") (class "Default")
      (node (ref "J1") (pin "12") (pinfunction "12_12") (pintype "passive"))
    )
    (net (code "109") (name "unconnected-(J1-Pad13)") (class "Default")
      (node (ref "J1") (pin "13") (pinfunction "13_13") (pintype "passive"))
    )
    (net (code "110") (name "unconnected-(J1-Pad14)") (class "Default")
      (node (ref "J1") (pin "14") (pinfunction "14_14") (pintype "passive"))
    )
    (net (code "111") (name "unconnected-(J1-Pad15)") (class "Default")
      (node (ref "J1") (pin "15") (pinfunction "15_15") (pintype "passive"))
    )
    (net (code "112") (name "unconnected-(J1-Pad16)") (class "Default")
      (node (ref "J1") (pin "16") (pinfunction "16_16") (pintype "passive"))
    )
    (net (code "113") (name "unconnected-(J1-Pad19)") (class "Default")
      (node (ref "J1") (pin "19") (pinfunction "19_19") (pintype "passive"))
    )
    (net (code "114") (name "unconnected-(J1-Pad20)") (class "Default")
      (node (ref "J1") (pin "20") (pinfunction "20_20") (pintype "passive"))
    )
    (net (code "115") (name "unconnected-(J2-Pad4)") (class "Default")
      (node (ref "J2") (pin "4") (pinfunction "4_4") (pintype "passive"))
    )
    (net (code "116") (name "unconnected-(J2-Pad5)") (class "Default")
      (node (ref "J2") (pin "5") (pinfunction "5_5") (pintype "passive"))
    )
    (net (code "117") (name "unconnected-(J2-Pad6)") (class "Default")
      (node (ref "J2") (pin "6") (pinfunction "6_6") (pintype "passive"))
    )
    (net (code "118") (name "unconnected-(J2-Pad7)") (class "Default")
      (node (ref "J2") (pin "7") (pinfunction "7_7") (pintype "passive"))
    )
    (net (code "119") (name "unconnected-(J2-Pad8)") (class "Default")
      (node (ref "J2") (pin "8") (pinfunction "8_8") (pintype "passive"))
    )
    (net (code "120") (name "unconnected-(J2-Pad9)") (class "Default")
      (node (ref "J2") (pin "9") (pinfunction "9_9") (pintype "passive"))
    )
    (net (code "121") (name "unconnected-(J2-Pad10)") (class "Default")
      (node (ref "J2") (pin "10") (pinfunction "10_10") (pintype "passive"))
    )
    (net (code "122") (name "unconnected-(J2-Pad11)") (class "Default")
      (node (ref "J2") (pin "11") (pinfunction "11_11") (pintype "passive"))
    )
    (net (code "123") (name "unconnected-(J2-Pad12)") (class "Default")
      (node (ref "J2") (pin "12") (pinfunction "12_12") (pintype "passive"))
    )
    (net (code "124") (name "unconnected-(J3-WAIT-Pad1)") (class "Default")
      (node (ref "J3-WAIT") (pin "1") (pinfunction "1_1") (pintype "passive"))
    )
    (net (code "125") (name "unconnected-(J3-WAIT-Pad2)") (class "Default")
      (node (ref "J3-WAIT") (pin "2") (pinfunction "2_2") (pintype "passive"))
    )
    (net (code "126") (name "unconnected-(J3-WAIT-Pad3)") (class "Default")
      (node (ref "J3-WAIT") (pin "3") (pinfunction "3_3") (pintype "passive"))
    )
    (net (code "127") (name "unconnected-(J3-WAIT-Pad5)") (class "Default")
      (node (ref "J3-WAIT") (pin "5") (pinfunction "5_5") (pintype "passive"))
    )
    (net (code "128") (name "unconnected-(J3-WAIT-Pad6)") (class "Default")
      (node (ref "J3-WAIT") (pin "6") (pinfunction "6_6") (pintype "passive"))
    )
    (net (code "129") (name "unconnected-(J3-WAIT-Pad7)") (class "Default")
      (node (ref "J3-WAIT") (pin "7") (pinfunction "7_7") (pintype "passive"))
    )
    (net (code "130") (name "unconnected-(J3-WAIT-Pad8)") (class "Default")
      (node (ref "J3-WAIT") (pin "8") (pinfunction "8_8") (pintype "passive"))
    )
    (net (code "131") (name "unconnected-(J4-INTERRUPTS-Pad1)") (class "Default")
      (node (ref "J4-INTERRUPTS") (pin "1") (pinfunction "1_1") (pintype "passive"))
    )
    (net (code "132") (name "unconnected-(J4-INTERRUPTS-Pad2)") (class "Default")
      (node (ref "J4-INTERRUPTS") (pin "2") (pinfunction "2_2") (pintype "passive"))
    )
    (net (code "133") (name "unconnected-(J4-INTERRUPTS-Pad3)") (class "Default")
      (node (ref "J4-INTERRUPTS") (pin "3") (pinfunction "3_3") (pintype "passive"))
    )
    (net (code "134") (name "unconnected-(J4-INTERRUPTS-Pad4)") (class "Default")
      (node (ref "J4-INTERRUPTS") (pin "4") (pinfunction "4_4") (pintype "passive"))
    )
    (net (code "135") (name "unconnected-(J4-INTERRUPTS-Pad5)") (class "Default")
      (node (ref "J4-INTERRUPTS") (pin "5") (pinfunction "5_5") (pintype "passive"))
    )
    (net (code "136") (name "unconnected-(J4-INTERRUPTS-Pad6)") (class "Default")
      (node (ref "J4-INTERRUPTS") (pin "6") (pinfunction "6_6") (pintype "passive"))
    )
    (net (code "137") (name "unconnected-(J4-INTERRUPTS-Pad7)") (class "Default")
      (node (ref "J4-INTERRUPTS") (pin "7") (pinfunction "7_7") (pintype "passive"))
    )
    (net (code "138") (name "unconnected-(J4-INTERRUPTS-Pad8)") (class "Default")
      (node (ref "J4-INTERRUPTS") (pin "8") (pinfunction "8_8") (pintype "passive"))
    )
    (net (code "139") (name "unconnected-(U$1-3V3-PadP$1)") (class "Default")
      (node (ref "U$1") (pin "P$1") (pinfunction "3V3_P$1") (pintype "bidirectional"))
    )
    (net (code "140") (name "unconnected-(U$1-CLK-PadP$20)") (class "Default")
      (node (ref "U$1") (pin "P$20") (pinfunction "CLK_P$20") (pintype "bidirectional"))
    )
    (net (code "141") (name "unconnected-(U$1-CMD-PadP$18)") (class "Default")
      (node (ref "U$1") (pin "P$18") (pinfunction "CMD_P$18") (pintype "bidirectional"))
    )
    (net (code "142") (name "unconnected-(U$1-EN-PadP$2)") (class "Default")
      (node (ref "U$1") (pin "P$2") (pinfunction "EN_P$2") (pintype "bidirectional"))
    )
    (net (code "143") (name "unconnected-(U$1-P2-PadP$24)") (class "Default")
      (node (ref "U$1") (pin "P$24") (pinfunction "P2_P$24") (pintype "bidirectional"))
    )
    (net (code "144") (name "unconnected-(U$1-P12-PadP$13)") (class "Default")
      (node (ref "U$1") (pin "P$13") (pinfunction "P12_P$13") (pintype "bidirectional"))
    )
    (net (code "145") (name "unconnected-(U$1-RX-PadP$34)") (class "Default")
      (node (ref "U$1") (pin "P$34") (pinfunction "RX_P$34") (pintype "bidirectional"))
    )
    (net (code "146") (name "unconnected-(U$1-SD0-PadP$21)") (class "Default")
      (node (ref "U$1") (pin "P$21") (pinfunction "SD0_P$21") (pintype "bidirectional"))
    )
    (net (code "147") (name "unconnected-(U$1-SD1-PadP$22)") (class "Default")
      (node (ref "U$1") (pin "P$22") (pinfunction "SD1_P$22") (pintype "bidirectional"))
    )
    (net (code "148") (name "unconnected-(U$1-SD2-PadP$16)") (class "Default")
      (node (ref "U$1") (pin "P$16") (pinfunction "SD2_P$16") (pintype "bidirectional"))
    )
    (net (code "149") (name "unconnected-(U$1-SD3-PadP$17)") (class "Default")
      (node (ref "U$1") (pin "P$17") (pinfunction "SD3_P$17") (pintype "bidirectional"))
    )
    (net (code "150") (name "unconnected-(U$1-SVN-PadP$4)") (class "Default")
      (node (ref "U$1") (pin "P$4") (pinfunction "SVN_P$4") (pintype "bidirectional"))
    )
    (net (code "151") (name "unconnected-(U$1-SVP-PadP$3)") (class "Default")
      (node (ref "U$1") (pin "P$3") (pinfunction "SVP_P$3") (pintype "bidirectional"))
    )
    (net (code "152") (name "unconnected-(U$1-TX-PadP$35)") (class "Default")
      (node (ref "U$1") (pin "P$35") (pinfunction "TX_P$35") (pintype "bidirectional"))
    )
  )
)
